# microphone_proto_routed.net
KiCad netlist of a schematic drawn in EAGLE
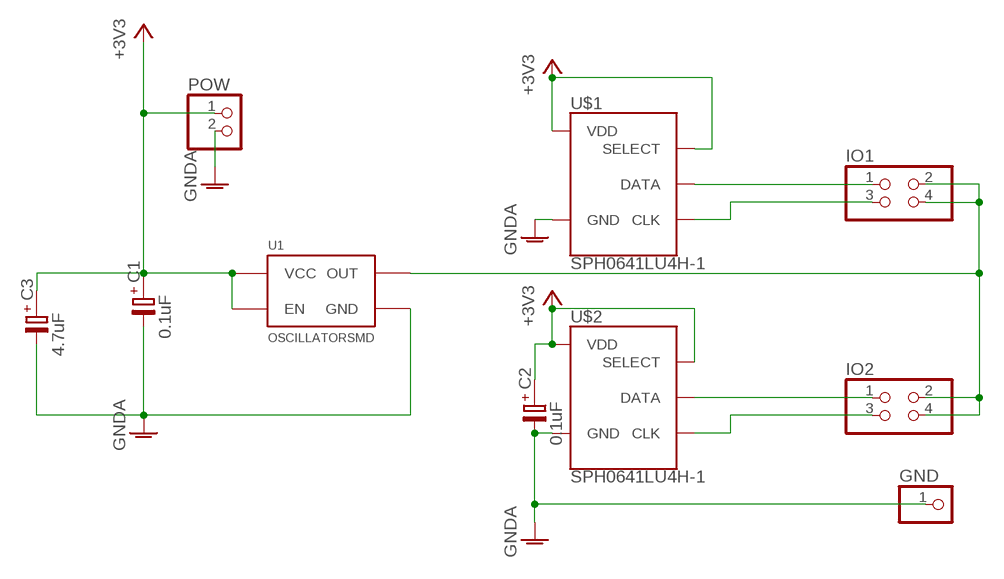
[diagram p0: schematic, sheet 1]

(export (version "E")
  (design (tool "Eeschema 10.0.6"))
  (components
    (comp (ref "C1")
      (value "0.1uF")
      (footprint "eagle-import:0805")
      (libsource (lib "eagle-import") (part "CPOL0805"))
    )
    (comp (ref "C2")
      (value "0.1uF")
      (footprint "eagle-import:0805")
      (libsource (lib "eagle-import") (part "CPOL0805"))
    )
    (comp (ref "C3")
      (value "4.7uF")
      (footprint "eagle-import:TE-A-3216")
      (libsource (lib "eagle-import") (part "CPOLA"))
    )
    (comp (ref "GND")
      (value "PINHD-1X1")
      (footprint "eagle-import:1X01")
      (libsource (lib "eagle-import") (part "PINHD-1X1"))
    )
    (comp (ref "IO1")
      (value "PINHD-2X2")
      (footprint "eagle-import:2X02")
      (libsource (lib "eagle-import") (part "PINHD-2X2"))
    )
    (comp (ref "IO2")
      (value "PINHD-2X2")
      (footprint "eagle-import:2X02")
      (libsource (lib "eagle-import") (part "PINHD-2X2"))
    )
    (comp (ref "POW")
      (value "PINHD-1X2")
      (footprint "eagle-import:1X02")
      (libsource (lib "eagle-import") (part "PINHD-1X2"))
    )
    (comp (ref "U$1")
      (value "SPH0641LU4H-1")
      (footprint "eagle-import:SPH0641LU4H-1")
      (libsource (lib "eagle-import") (part "SPH0641LU4H-1"))
    )
    (comp (ref "U$2")
      (value "SPH0641LU4H-1")
      (footprint "eagle-import:SPH0641LU4H-1")
      (libsource (lib "eagle-import") (part "SPH0641LU4H-1"))
    )
    (comp (ref "U1")
      (value "OSCILLATORSMD")
      (footprint "eagle-import:CRYSTAL-SMD-7X5")
      (libsource (lib "eagle-import") (part "OSCILLATORSMD"))
    )
  )
  (nets
    (net (code "1") (name "+3V3") (class "Default")
      (node (ref "C1") (pin "+") (pinfunction "+_+") (pintype "passive"))
      (node (ref "C2") (pin "+") (pinfunction "+_+") (pintype "passive"))
      (node (ref "C3") (pin "+") (pinfunction "+_+") (pintype "passive"))
      (node (ref "POW") (pin "1") (pinfunction "1_1") (pintype "passive"))
      (node (ref "U$1") (pin "2") (pinfunction "SELECT_2") (pintype "bidirectional"))
      (node (ref "U$1") (pin "5") (pinfunction "VDD_5") (pintype "bidirectional"))
      (node (ref "U$2") (pin "2") (pinfunction "SELECT_2") (pintype "bidirectional"))
      (node (ref "U$2") (pin "5") (pinfunction "VDD_5") (pintype "bidirectional"))
      (node (ref "U1") (pin "P$1") (pinfunction "EN_P$1") (pintype "bidirectional"))
      (node (ref "U1") (pin "P$4") (pinfunction "VCC_P$4") (pintype "bidirectional"))
    )
    (net (code "2") (name "GNDA") (class "Default")
      (node (ref "C1") (pin "-") (pinfunction "-_-") (pintype "passive"))
      (node (ref "C2") (pin "-") (pinfunction "-_-") (pintype "passive"))
      (node (ref "C3") (pin "-") (pinfunction "-_-") (pintype "passive"))
      (node (ref "GND") (pin "1") (pinfunction "1_1") (pintype "passive"))
      (node (ref "POW") (pin "2") (pinfunction "2_2") (pintype "passive"))
      (node (ref "U$1") (pin "3") (pinfunction "GND_3") (pintype "bidirectional"))
      (node (ref "U$2") (pin "3") (pinfunction "GND_3") (pintype "bidirectional"))
      (node (ref "U1") (pin "P$2") (pinfunction "GND_P$2") (pintype "bidirectional"))
    )
    (net (code "3") (name "Net-(U$1-CLK)") (class "Default")
      (node (ref "IO1") (pin "3") (pinfunction "3_3") (pintype "passive"))
      (node (ref "U$1") (pin "4") (pinfunction "CLK_4") (pintype "bidirectional"))
    )
    (net (code "4") (name "Net-(U$1-DATA)") (class "Default")
      (node (ref "IO1") (pin "1") (pinfunction "1_1") (pintype "passive"))
      (node (ref "U$1") (pin "1") (pinfunction "DATA_1") (pintype "bidirectional"))
    )
    (net (code "5") (name "Net-(U$2-CLK)") (class "Default")
      (node (ref "IO2") (pin "3") (pinfunction "3_3") (pintype "passive"))
      (node (ref "U$2") (pin "4") (pinfunction "CLK_4") (pintype "bidirectional"))
    )
    (net (code "6") (name "Net-(U$2-DATA)") (class "Default")
      (node (ref "IO2") (pin "1") (pinfunction "1_1") (pintype "passive"))
      (node (ref "U$2") (pin "1") (pinfunction "DATA_1") (pintype "bidirectional"))
    )
    (net (code "7") (name "Net-(U1-OUT)") (class "Default")
      (node (ref "IO1") (pin "2") (pinfunction "2_2") (pintype "passive"))
      (node (ref "IO1") (pin "4") (pinfunction "4_4") (pintype "passive"))
      (node (ref "IO2") (pin "2") (pinfunction "2_2") (pintype "passive"))
      (node (ref "IO2") (pin "4") (pinfunction "4_4") (pintype "passive"))
      (node (ref "U1") (pin "P$3") (pinfunction "OUT_P$3") (pintype "bidirectional"))
    )
  )
)
